# howland_vccs_single_ended.net
KiCad netlist of a schematic drawn in EAGLE
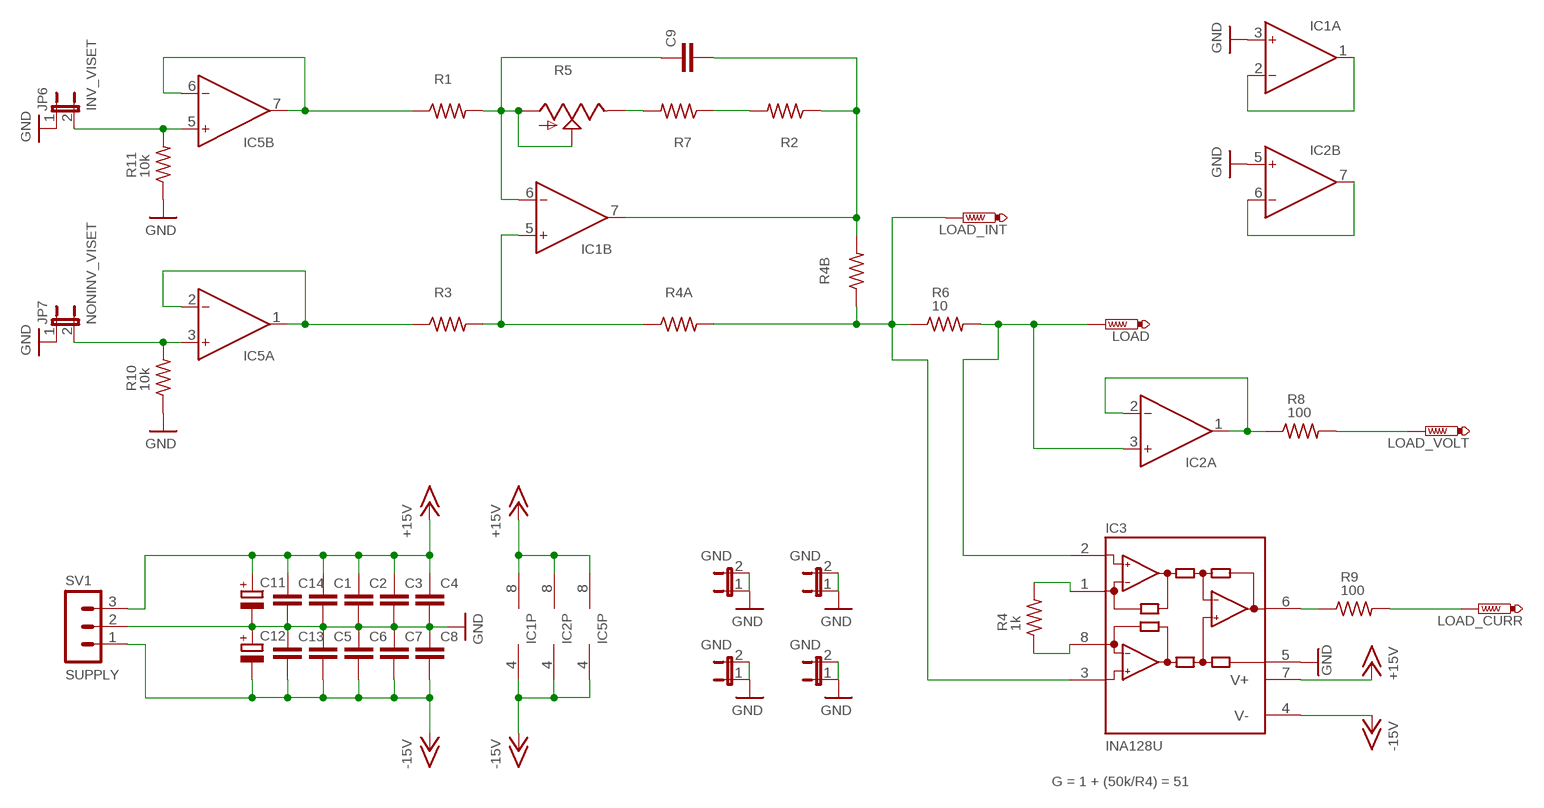
[diagram p0: schematic, sheet 1]

(export (version "E")
  (design (tool "Eeschema 10.0.6"))
  (components
    (comp (ref "C1")
      (value "C-EUC1206")
      (footprint "eagle-import:C1206")
      (libsource (lib "eagle-import") (part "C-EUC1206"))
    )
    (comp (ref "C2")
      (value "C-EUC1206")
      (footprint "eagle-import:C1206")
      (libsource (lib "eagle-import") (part "C-EUC1206"))
    )
    (comp (ref "C3")
      (value "C-EUC1206")
      (footprint "eagle-import:C1206")
      (libsource (lib "eagle-import") (part "C-EUC1206"))
    )
    (comp (ref "C4")
      (value "C-EUC1206")
      (footprint "eagle-import:C1206")
      (libsource (lib "eagle-import") (part "C-EUC1206"))
    )
    (comp (ref "C5")
      (value "C-EUC1206")
      (footprint "eagle-import:C1206")
      (libsource (lib "eagle-import") (part "C-EUC1206"))
    )
    (comp (ref "C6")
      (value "C-EUC1206")
      (footprint "eagle-import:C1206")
      (libsource (lib "eagle-import") (part "C-EUC1206"))
    )
    (comp (ref "C7")
      (value "C-EUC1206")
      (footprint "eagle-import:C1206")
      (libsource (lib "eagle-import") (part "C-EUC1206"))
    )
    (comp (ref "C8")
      (value "C-EUC1206")
      (footprint "eagle-import:C1206")
      (libsource (lib "eagle-import") (part "C-EUC1206"))
    )
    (comp (ref "C9")
      (value "C-EUC1206")
      (footprint "eagle-import:C1206")
      (libsource (lib "eagle-import") (part "C-EUC1206"))
    )
    (comp (ref "C11")
      (value "CPOL-EUC/6032-28R")
      (footprint "eagle-import:C_6032-28R")
      (libsource (lib "eagle-import") (part "CPOL-EUC/6032-28R"))
    )
    (comp (ref "C12")
      (value "CPOL-EUC/6032-28R")
      (footprint "eagle-import:C_6032-28R")
      (libsource (lib "eagle-import") (part "CPOL-EUC/6032-28R"))
    )
    (comp (ref "C13")
      (value "C-EUC1206")
      (footprint "eagle-import:C1206")
      (libsource (lib "eagle-import") (part "C-EUC1206"))
    )
    (comp (ref "C14")
      (value "C-EUC1206")
      (footprint "eagle-import:C1206")
      (libsource (lib "eagle-import") (part "C-EUC1206"))
    )
    (comp (ref "IC1")
      (value "LM358")
      (footprint "eagle-import:SO8")
      (fields (field (name "MF") "ALTERA CORPORATION") (field (name "MPN") "AD826AR"))
      (libsource (lib "eagle-import") (part "AD826R"))
    )
    (comp (ref "IC2")
      (value "LM358")
      (footprint "eagle-import:SO8")
      (fields (field (name "MF") "ALTERA CORPORATION") (field (name "MPN") "AD826AR"))
      (libsource (lib "eagle-import") (part "AD826R"))
    )
    (comp (ref "IC3")
      (value "INA128U")
      (footprint "eagle-import:SO08")
      (fields (field (name "MF") "TEXAS INSTRUMENTS"))
      (libsource (lib "eagle-import") (part "INA128U"))
    )
    (comp (ref "IC5")
      (value "OPA2192")
      (footprint "eagle-import:SO8")
      (fields (field (name "MF") "ALTERA CORPORATION") (field (name "MPN") "AD826AR"))
      (libsource (lib "eagle-import") (part "AD826R"))
    )
    (comp (ref "JP4")
      (value "GND")
      (footprint "eagle-import:JP1")
      (libsource (lib "eagle-import") (part "JP1E"))
    )
    (comp (ref "JP6")
      (value "INV_VISET")
      (footprint "eagle-import:JP1")
      (libsource (lib "eagle-import") (part "JP1E"))
    )
    (comp (ref "JP7")
      (value "NONINV_VISET")
      (footprint "eagle-import:JP1")
      (libsource (lib "eagle-import") (part "JP1E"))
    )
    (comp (ref "JP8")
      (value "GND")
      (footprint "eagle-import:JP1")
      (libsource (lib "eagle-import") (part "JP1E"))
    )
    (comp (ref "JP9")
      (value "GND")
      (footprint "eagle-import:JP1")
      (libsource (lib "eagle-import") (part "JP1E"))
    )
    (comp (ref "JP10")
      (value "GND")
      (footprint "eagle-import:JP1")
      (libsource (lib "eagle-import") (part "JP1E"))
    )
    (comp (ref "LOAD")
      (value "PTR1PAD1-13")
      (footprint "eagle-import:P1-13")
      (libsource (lib "eagle-import") (part "PTR1PAD1-13"))
    )
    (comp (ref "LOAD_CURR")
      (value "PTR1PAD1-13")
      (footprint "eagle-import:P1-13")
      (libsource (lib "eagle-import") (part "PTR1PAD1-13"))
    )
    (comp (ref "LOAD_INT")
      (value "PTR1PAD1-13")
      (footprint "eagle-import:P1-13")
      (libsource (lib "eagle-import") (part "PTR1PAD1-13"))
    )
    (comp (ref "LOAD_VOLT")
      (value "PTR1PAD1-13")
      (footprint "eagle-import:P1-13")
      (libsource (lib "eagle-import") (part "PTR1PAD1-13"))
    )
    (comp (ref "R1")
      (value "12.25k/0.1%")
      (footprint "eagle-import:R1206")
      (libsource (lib "eagle-import") (part "R-US_R1206"))
    )
    (comp (ref "R2")
      (value "10k/.1%")
      (footprint "eagle-import:R1206")
      (libsource (lib "eagle-import") (part "R-US_R1206"))
    )
    (comp (ref "R3")
      (value "12.25k/0.1%")
      (footprint "eagle-import:R1206")
      (libsource (lib "eagle-import") (part "R-US_R1206"))
    )
    (comp (ref "R4")
      (value "1k")
      (footprint "eagle-import:R1206")
      (libsource (lib "eagle-import") (part "R-US_R1206"))
    )
    (comp (ref "R4A")
      (value "10k/.1%")
      (footprint "eagle-import:R1206")
      (libsource (lib "eagle-import") (part "R-US_R1206"))
    )
    (comp (ref "R4B")
      (value "250")
      (footprint "eagle-import:R1206")
      (libsource (lib "eagle-import") (part "R-US_R1206"))
    )
    (comp (ref "R5")
      (value "100")
      (footprint "eagle-import:3223J")
      (libsource (lib "eagle-import") (part "TRIM_US-3223J"))
    )
    (comp (ref "R6")
      (value "10")
      (footprint "eagle-import:R1206")
      (libsource (lib "eagle-import") (part "R-US_R1206"))
    )
    (comp (ref "R7")
      (value "200")
      (footprint "eagle-import:R1206")
      (libsource (lib "eagle-import") (part "R-US_R1206"))
    )
    (comp (ref "R8")
      (value "100")
      (footprint "eagle-import:R1206")
      (libsource (lib "eagle-import") (part "R-US_R1206"))
    )
    (comp (ref "R9")
      (value "100")
      (footprint "eagle-import:R1206")
      (libsource (lib "eagle-import") (part "R-US_R1206"))
    )
    (comp (ref "R10")
      (value "10k")
      (footprint "eagle-import:R1206")
      (libsource (lib "eagle-import") (part "R-US_R1206"))
    )
    (comp (ref "R11")
      (value "10k")
      (footprint "eagle-import:R1206")
      (libsource (lib "eagle-import") (part "R-US_R1206"))
    )
    (comp (ref "SV1")
      (value "SUPPLY")
      (footprint "eagle-import:MA03-1")
      (libsource (lib "eagle-import") (part "MA03-1"))
    )
  )
  (nets
    (net (code "1") (name "+15V") (class "Default")
      (node (ref "C1") (pin "1") (pinfunction "1_1") (pintype "passive"))
      (node (ref "C11") (pin "+") (pinfunction "+_+") (pintype "passive"))
      (node (ref "C14") (pin "1") (pinfunction "1_1") (pintype "passive"))
      (node (ref "C2") (pin "1") (pinfunction "1_1") (pintype "passive"))
      (node (ref "C3") (pin "1") (pinfunction "1_1") (pintype "passive"))
      (node (ref "C4") (pin "1") (pinfunction "1_1") (pintype "passive"))
      (node (ref "IC1") (pin "8") (pinfunction "V+_8") (pintype "power_in"))
      (node (ref "IC2") (pin "8") (pinfunction "V+_8") (pintype "power_in"))
      (node (ref "IC3") (pin "7") (pinfunction "V+_7") (pintype "power_in"))
      (node (ref "IC5") (pin "8") (pinfunction "V+_8") (pintype "power_in"))
      (node (ref "SV1") (pin "3") (pinfunction "3_3") (pintype "passive"))
    )
    (net (code "2") (name "-15V") (class "Default")
      (node (ref "C12") (pin "-") (pinfunction "-_-") (pintype "passive"))
      (node (ref "C13") (pin "2") (pinfunction "2_2") (pintype "passive"))
      (node (ref "C5") (pin "2") (pinfunction "2_2") (pintype "passive"))
      (node (ref "C6") (pin "2") (pinfunction "2_2") (pintype "passive"))
      (node (ref "C7") (pin "2") (pinfunction "2_2") (pintype "passive"))
      (node (ref "C8") (pin "2") (pinfunction "2_2") (pintype "passive"))
      (node (ref "IC1") (pin "4") (pinfunction "V-_4") (pintype "power_in"))
      (node (ref "IC2") (pin "4") (pinfunction "V-_4") (pintype "power_in"))
      (node (ref "IC3") (pin "4") (pinfunction "V-_4") (pintype "power_in"))
      (node (ref "IC5") (pin "4") (pinfunction "V-_4") (pintype "power_in"))
      (node (ref "SV1") (pin "1") (pinfunction "1_1") (pintype "passive"))
    )
    (net (code "3") (name "GND") (class "Default")
      (node (ref "C1") (pin "2") (pinfunction "2_2") (pintype "passive"))
      (node (ref "C11") (pin "-") (pinfunction "-_-") (pintype "passive"))
      (node (ref "C12") (pin "+") (pinfunction "+_+") (pintype "passive"))
      (node (ref "C13") (pin "1") (pinfunction "1_1") (pintype "passive"))
      (node (ref "C14") (pin "2") (pinfunction "2_2") (pintype "passive"))
      (node (ref "C2") (pin "2") (pinfunction "2_2") (pintype "passive"))
      (node (ref "C3") (pin "2") (pinfunction "2_2") (pintype "passive"))
      (node (ref "C4") (pin "2") (pinfunction "2_2") (pintype "passive"))
      (node (ref "C5") (pin "1") (pinfunction "1_1") (pintype "passive"))
      (node (ref "C6") (pin "1") (pinfunction "1_1") (pintype "passive"))
      (node (ref "C7") (pin "1") (pinfunction "1_1") (pintype "passive"))
      (node (ref "C8") (pin "1") (pinfunction "1_1") (pintype "passive"))
      (node (ref "IC1") (pin "3") (pinfunction "IN+_3") (pintype "input"))
      (node (ref "IC2") (pin "5") (pinfunction "IN+_5") (pintype "input"))
      (node (ref "IC3") (pin "5") (pinfunction "REF_5") (pintype "passive"))
      (node (ref "JP10") (pin "1") (pinfunction "1_1") (pintype "passive"))
      (node (ref "JP10") (pin "2") (pinfunction "2_2") (pintype "passive"))
      (node (ref "JP4") (pin "1") (pinfunction "1_1") (pintype "passive"))
      (node (ref "JP4") (pin "2") (pinfunction "2_2") (pintype "passive"))
      (node (ref "JP6") (pin "1") (pinfunction "1_1") (pintype "passive"))
      (node (ref "JP7") (pin "1") (pinfunction "1_1") (pintype "passive"))
      (node (ref "JP8") (pin "1") (pinfunction "1_1") (pintype "passive"))
      (node (ref "JP8") (pin "2") (pinfunction "2_2") (pintype "passive"))
      (node (ref "JP9") (pin "1") (pinfunction "1_1") (pintype "passive"))
      (node (ref "JP9") (pin "2") (pinfunction "2_2") (pintype "passive"))
      (node (ref "R10") (pin "1") (pinfunction "1_1") (pintype "passive"))
      (node (ref "R11") (pin "1") (pinfunction "1_1") (pintype "passive"))
      (node (ref "SV1") (pin "2") (pinfunction "2_2") (pintype "passive"))
    )
    (net (code "4") (name "Net-(IC1A-IN-)") (class "Default")
      (node (ref "IC1") (pin "1") (pinfunction "OUT_1") (pintype "output"))
      (node (ref "IC1") (pin "2") (pinfunction "IN-_2") (pintype "input"))
    )
    (net (code "5") (name "Net-(IC1B-IN+)") (class "Default")
      (node (ref "IC1") (pin "5") (pinfunction "IN+_5") (pintype "input"))
      (node (ref "R3") (pin "2") (pinfunction "2_2") (pintype "passive"))
      (node (ref "R4A") (pin "1") (pinfunction "1_1") (pintype "passive"))
    )
    (net (code "6") (name "Net-(IC1B-IN-)") (class "Default")
      (node (ref "C9") (pin "1") (pinfunction "1_1") (pintype "passive"))
      (node (ref "IC1") (pin "6") (pinfunction "IN-_6") (pintype "input"))
      (node (ref "R1") (pin "2") (pinfunction "2_2") (pintype "passive"))
      (node (ref "R5") (pin "1") (pinfunction "A_1") (pintype "passive"))
      (node (ref "R5") (pin "2") (pinfunction "S_2") (pintype "passive"))
    )
    (net (code "7") (name "Net-(IC1B-OUT)") (class "Default")
      (node (ref "C9") (pin "2") (pinfunction "2_2") (pintype "passive"))
      (node (ref "IC1") (pin "7") (pinfunction "OUT_7") (pintype "output"))
      (node (ref "R2") (pin "1") (pinfunction "1_1") (pintype "passive"))
      (node (ref "R4B") (pin "2") (pinfunction "2_2") (pintype "passive"))
    )
    (net (code "8") (name "Net-(IC2A-IN+)") (class "Default")
      (node (ref "IC2") (pin "3") (pinfunction "IN+_3") (pintype "input"))
      (node (ref "IC3") (pin "2") (pinfunction "-IN_2") (pintype "input"))
      (node (ref "LOAD") (pin "TP") (pinfunction "TP_TP") (pintype "input"))
      (node (ref "R6") (pin "2") (pinfunction "2_2") (pintype "passive"))
    )
    (net (code "9") (name "Net-(IC2A-IN-)") (class "Default")
      (node (ref "IC2") (pin "1") (pinfunction "OUT_1") (pintype "output"))
      (node (ref "IC2") (pin "2") (pinfunction "IN-_2") (pintype "input"))
      (node (ref "R8") (pin "1") (pinfunction "1_1") (pintype "passive"))
    )
    (net (code "10") (name "Net-(IC2B-IN-)") (class "Default")
      (node (ref "IC2") (pin "6") (pinfunction "IN-_6") (pintype "input"))
      (node (ref "IC2") (pin "7") (pinfunction "OUT_7") (pintype "output"))
    )
    (net (code "11") (name "Net-(IC3-+IN)") (class "Default")
      (node (ref "IC3") (pin "3") (pinfunction "+IN_3") (pintype "input"))
      (node (ref "LOAD_INT") (pin "TP") (pinfunction "TP_TP") (pintype "input"))
      (node (ref "R4A") (pin "2") (pinfunction "2_2") (pintype "passive"))
      (node (ref "R4B") (pin "1") (pinfunction "1_1") (pintype "passive"))
      (node (ref "R6") (pin "1") (pinfunction "1_1") (pintype "passive"))
    )
    (net (code "12") (name "Net-(IC3-OUT)") (class "Default")
      (node (ref "IC3") (pin "6") (pinfunction "OUT_6") (pintype "output"))
      (node (ref "R9") (pin "1") (pinfunction "1_1") (pintype "passive"))
    )
    (net (code "13") (name "Net-(IC3-RG-Pad1)") (class "Default")
      (node (ref "IC3") (pin "1") (pinfunction "RG_1") (pintype "passive"))
      (node (ref "R4") (pin "2") (pinfunction "2_2") (pintype "passive"))
    )
    (net (code "14") (name "Net-(IC3-RG-Pad8)") (class "Default")
      (node (ref "IC3") (pin "8") (pinfunction "RG_8") (pintype "passive"))
      (node (ref "R4") (pin "1") (pinfunction "1_1") (pintype "passive"))
    )
    (net (code "15") (name "Net-(IC5A-IN+)") (class "Default")
      (node (ref "IC5") (pin "3") (pinfunction "IN+_3") (pintype "input"))
      (node (ref "JP7") (pin "2") (pinfunction "2_2") (pintype "passive"))
      (node (ref "R10") (pin "2") (pinfunction "2_2") (pintype "passive"))
    )
    (net (code "16") (name "Net-(IC5A-IN-)") (class "Default")
      (node (ref "IC5") (pin "1") (pinfunction "OUT_1") (pintype "output"))
      (node (ref "IC5") (pin "2") (pinfunction "IN-_2") (pintype "input"))
      (node (ref "R3") (pin "1") (pinfunction "1_1") (pintype "passive"))
    )
    (net (code "17") (name "Net-(IC5B-IN+)") (class "Default")
      (node (ref "IC5") (pin "5") (pinfunction "IN+_5") (pintype "input"))
      (node (ref "JP6") (pin "2") (pinfunction "2_2") (pintype "passive"))
      (node (ref "R11") (pin "2") (pinfunction "2_2") (pintype "passive"))
    )
    (net (code "18") (name "Net-(IC5B-IN-)") (class "Default")
      (node (ref "IC5") (pin "6") (pinfunction "IN-_6") (pintype "input"))
      (node (ref "IC5") (pin "7") (pinfunction "OUT_7") (pintype "output"))
      (node (ref "R1") (pin "1") (pinfunction "1_1") (pintype "passive"))
    )
    (net (code "19") (name "Net-(LOAD_CURR-PadTP)") (class "Default")
      (node (ref "LOAD_CURR") (pin "TP") (pinfunction "TP_TP") (pintype "input"))
      (node (ref "R9") (pin "2") (pinfunction "2_2") (pintype "passive"))
    )
    (net (code "20") (name "Net-(LOAD_VOLT-PadTP)") (class "Default")
      (node (ref "LOAD_VOLT") (pin "TP") (pinfunction "TP_TP") (pintype "input"))
      (node (ref "R8") (pin "2") (pinfunction "2_2") (pintype "passive"))
    )
    (net (code "21") (name "Net-(R2-Pad2)") (class "Default")
      (node (ref "R2") (pin "2") (pinfunction "2_2") (pintype "passive"))
      (node (ref "R7") (pin "1") (pinfunction "1_1") (pintype "passive"))
    )
    (net (code "22") (name "Net-(R5-E)") (class "Default")
      (node (ref "R5") (pin "3") (pinfunction "E_3") (pintype "passive"))
      (node (ref "R7") (pin "2") (pinfunction "2_2") (pintype "passive"))
    )
  )
)
